# MyLightThingy.net
KiCad netlist of a schematic drawn in EasyEDA Pro
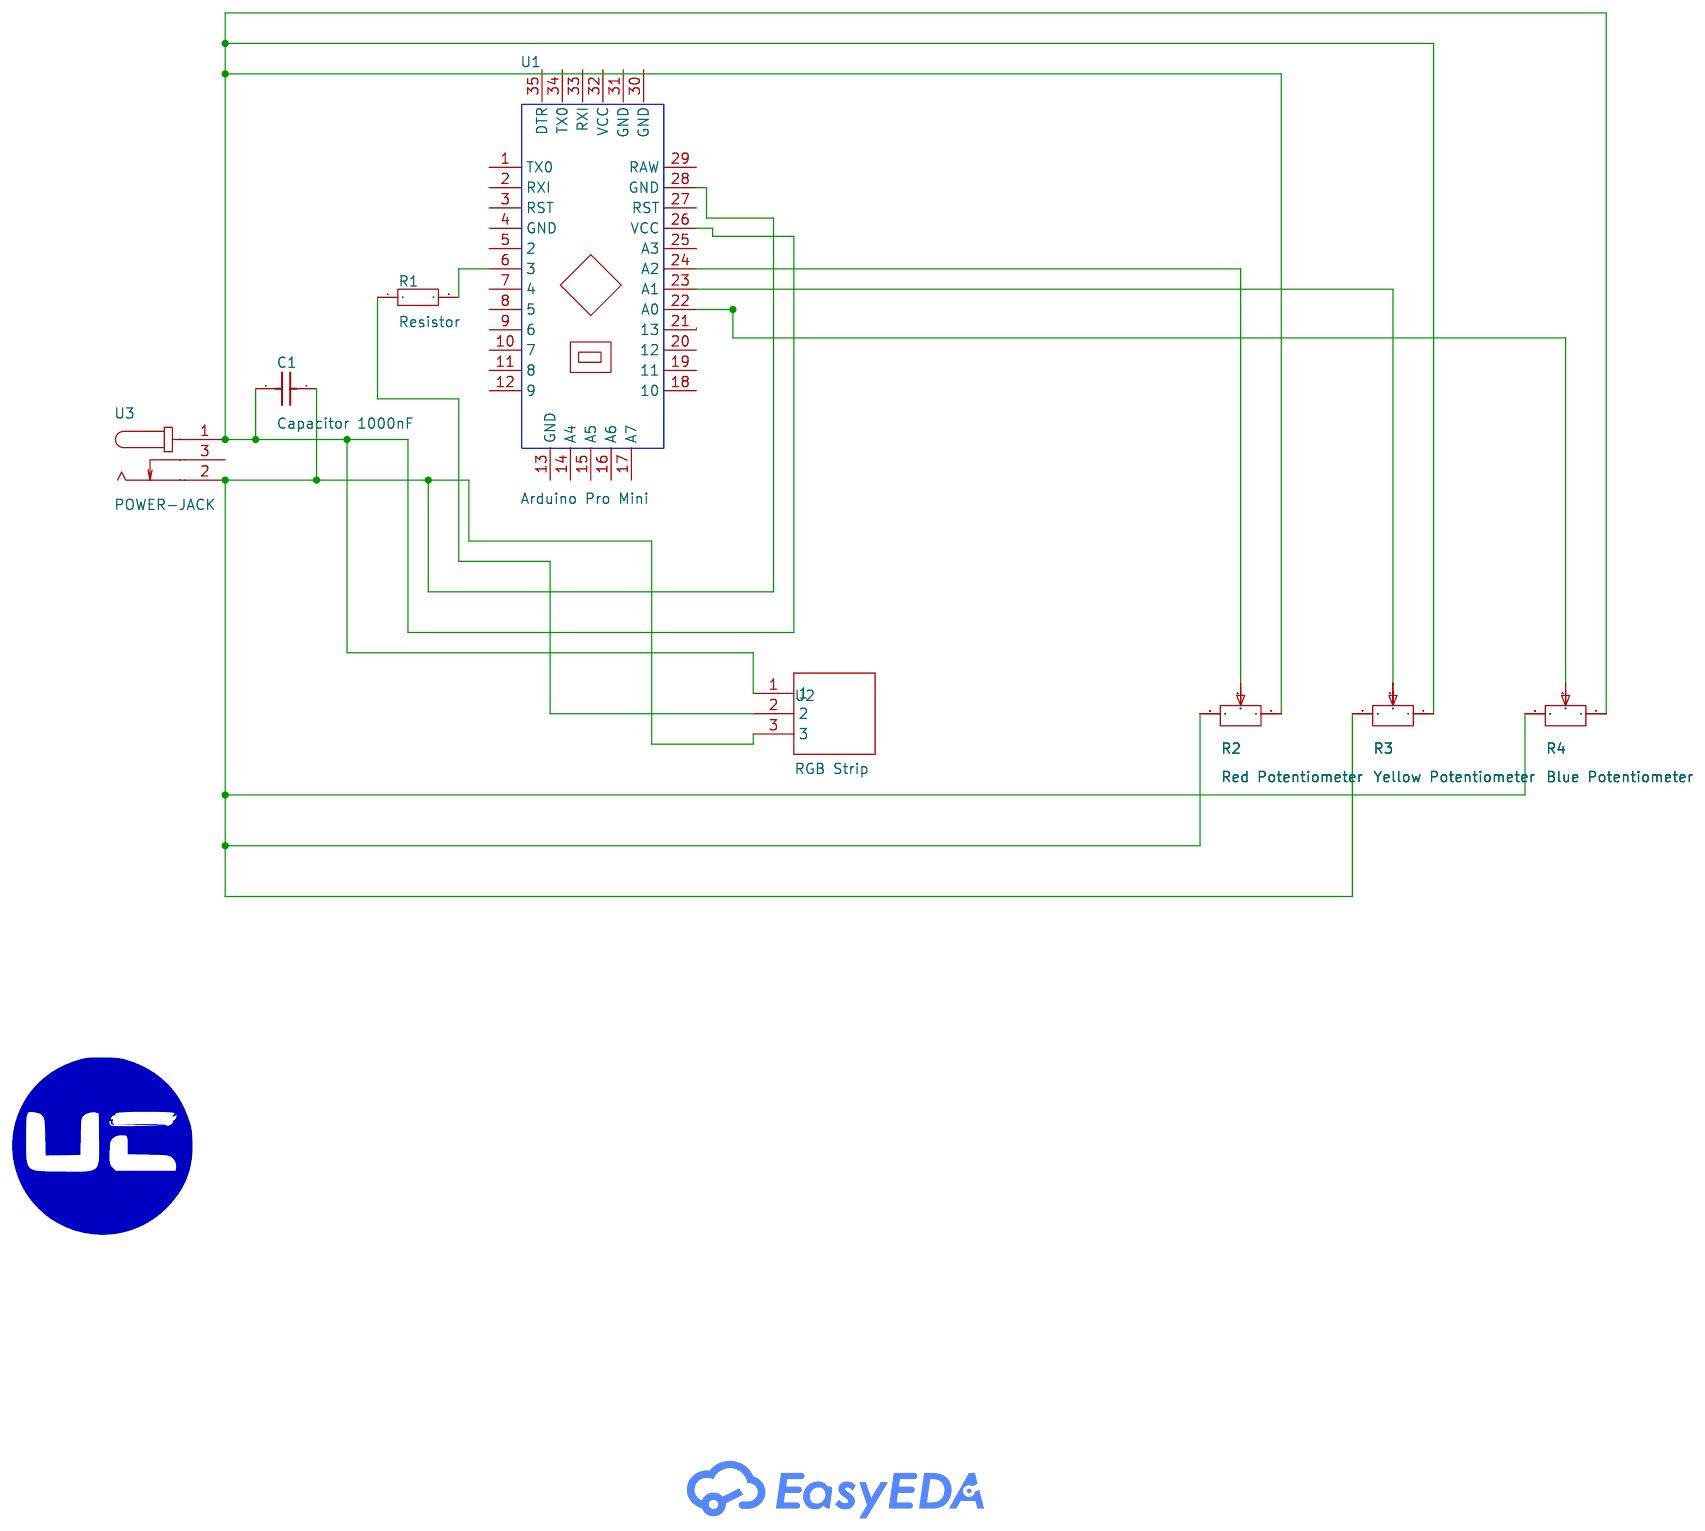
[diagram p0: schematic sheet]

(export (version "E")
  (design (tool "Eeschema 10.0.6"))
  (components
    (comp (ref "C1")
      (value "Capacitor 1000nF")
      (footprint "easyedapro:CAP-TH_L7.2-W2.5-P5.00-D0.5_224CL0016")
      (description "1pf - 100nf box film cap")
      (fields
        (field (name "Manufacturer Part") "CL21B104KCFNNNE")
        (field (name "Manufacturer") "SAMSUNG(三星)")
      )
      (libsource (lib "easyedapro") (part "Avg Film cap"))
    )
    (comp (ref "R1")
      (value "Resistor")
      (footprint "easyedapro:Resistor 1/8w 7mm metal film")
      (fields
        (field (name "Manufacturer Part") "1206W4F1002T5E")
        (field (name "Manufacturer") "UNI-ROYAL(Uniroyal Elec)")
      )
      (libsource (lib "easyedapro") (part "resistor"))
    )
    (comp (ref "R2")
      (value "10kΩ")
      (footprint "easyedapro:RES-ADJ-TH_RK1631110TT3")
      (description "Resistance: Tolerance:±20% Tolerance:±20% Power(Watts):50mW Turns:- Rated Voltage:5V")
      (fields
        (field (name "Manufacturer Part") "RK1631110TT3")
        (field (name "Manufacturer") "ALPSALPINE(阿尔卑斯阿尔派)")
      )
      (libsource (lib "easyedapro") (part "Potentiometer"))
    )
    (comp (ref "R3")
      (value "10kΩ")
      (footprint "easyedapro:RES-ADJ-TH_RK1631110TT3")
      (description "Resistance: Tolerance:±20% Tolerance:±20% Power(Watts):50mW Turns:- Rated Voltage:5V")
      (fields
        (field (name "Manufacturer Part") "RK1631110TT3")
        (field (name "Manufacturer") "ALPSALPINE(阿尔卑斯阿尔派)")
      )
      (libsource (lib "easyedapro") (part "Potentiometer"))
    )
    (comp (ref "R4")
      (value "10kΩ")
      (footprint "easyedapro:RES-ADJ-TH_RK1631110TT3")
      (description "Resistance: Tolerance:±20% Tolerance:±20% Power(Watts):50mW Turns:- Rated Voltage:5V")
      (fields
        (field (name "Manufacturer Part") "RK1631110TT3")
        (field (name "Manufacturer") "ALPSALPINE(阿尔卑斯阿尔派)")
      )
      (libsource (lib "easyedapro") (part "Potentiometer"))
    )
    (comp (ref "U1")
      (value "Arduino Pro Mini")
      (footprint "easyedapro:Arduino_Pro_Mini")
      (libsource (lib "easyedapro") (part "Arduino Pro Mini"))
    )
    (comp (ref "U2")
      (value "RGB Strip")
      (footprint "easyedapro:V3 pin male 3x1")
      (fields (field (name "Manufacturer") "TE Connectivity"))
      (libsource (lib "easyedapro") (part "V3 pin male 3x1"))
    )
    (comp (ref "U3")
      (value "POWER-JACK")
      (footprint "easyedapro:DC-IN-TH_POWER-JACK")
      (libsource (lib "easyedapro") (part "POWER-JACK"))
    )
  )
  (nets
    (net (code "1") (name "Net-(C1-Pad1)") (class "Default")
      (node (ref "C1") (pin "1") (pinfunction "1_1") (pintype "input"))
      (node (ref "R2") (pin "1") (pinfunction "1_1") (pintype "input"))
      (node (ref "R3") (pin "1") (pinfunction "1_1") (pintype "input"))
      (node (ref "R4") (pin "1") (pinfunction "1_1") (pintype "input"))
      (node (ref "U1") (pin "26") (pinfunction "VCC_26") (pintype "input"))
      (node (ref "U2") (pin "1") (pinfunction "1_1") (pintype "bidirectional"))
      (node (ref "U3") (pin "1") (pinfunction "1_1") (pintype "unspecified"))
    )
    (net (code "2") (name "Net-(C1-Pad2)") (class "Default")
      (node (ref "C1") (pin "2") (pinfunction "2_2") (pintype "input"))
      (node (ref "R2") (pin "3") (pinfunction "3_3") (pintype "input"))
      (node (ref "R3") (pin "3") (pinfunction "3_3") (pintype "input"))
      (node (ref "R4") (pin "3") (pinfunction "3_3") (pintype "input"))
      (node (ref "U1") (pin "28") (pinfunction "GND_28") (pintype "input"))
      (node (ref "U2") (pin "3") (pinfunction "3_3") (pintype "bidirectional"))
      (node (ref "U3") (pin "2") (pinfunction "2_2") (pintype "unspecified"))
    )
    (net (code "3") (name "Net-(R1-Pad1)") (class "Default")
      (node (ref "R1") (pin "1") (pinfunction "1_1") (pintype "input"))
      (node (ref "U2") (pin "2") (pinfunction "2_2") (pintype "bidirectional"))
    )
    (net (code "4") (name "Net-(U1-3)") (class "Default")
      (node (ref "R1") (pin "2") (pinfunction "2_2") (pintype "input"))
      (node (ref "U1") (pin "6") (pinfunction "3_6") (pintype "input"))
    )
    (net (code "5") (name "Net-(U1-A0)") (class "Default")
      (node (ref "R4") (pin "2") (pinfunction "2_2") (pintype "input"))
      (node (ref "U1") (pin "22") (pinfunction "A0_22") (pintype "input"))
    )
    (net (code "6") (name "Net-(U1-A1)") (class "Default")
      (node (ref "R3") (pin "2") (pinfunction "2_2") (pintype "input"))
      (node (ref "U1") (pin "23") (pinfunction "A1_23") (pintype "input"))
    )
    (net (code "7") (name "Net-(U1-A2)") (class "Default")
      (node (ref "R2") (pin "2") (pinfunction "2_2") (pintype "input"))
      (node (ref "U1") (pin "24") (pinfunction "A2_24") (pintype "input"))
    )
    (net (code "8") (name "unconnected-(U1-2-Pad5)") (class "Default")
      (node (ref "U1") (pin "5") (pinfunction "2_5") (pintype "input"))
    )
    (net (code "9") (name "unconnected-(U1-4-Pad7)") (class "Default")
      (node (ref "U1") (pin "7") (pinfunction "4_7") (pintype "input"))
    )
    (net (code "10") (name "unconnected-(U1-5-Pad8)") (class "Default")
      (node (ref "U1") (pin "8") (pinfunction "5_8") (pintype "input"))
    )
    (net (code "11") (name "unconnected-(U1-6-Pad9)") (class "Default")
      (node (ref "U1") (pin "9") (pinfunction "6_9") (pintype "input"))
    )
    (net (code "12") (name "unconnected-(U1-7-Pad10)") (class "Default")
      (node (ref "U1") (pin "10") (pinfunction "7_10") (pintype "input"))
    )
    (net (code "13") (name "unconnected-(U1-8-Pad11)") (class "Default")
      (node (ref "U1") (pin "11") (pinfunction "8_11") (pintype "input"))
    )
    (net (code "14") (name "unconnected-(U1-9-Pad12)") (class "Default")
      (node (ref "U1") (pin "12") (pinfunction "9_12") (pintype "input"))
    )
    (net (code "15") (name "unconnected-(U1-10-Pad18)") (class "Default")
      (node (ref "U1") (pin "18") (pinfunction "10_18") (pintype "input"))
    )
    (net (code "16") (name "unconnected-(U1-11-Pad19)") (class "Default")
      (node (ref "U1") (pin "19") (pinfunction "11_19") (pintype "input"))
    )
    (net (code "17") (name "unconnected-(U1-12-Pad20)") (class "Default")
      (node (ref "U1") (pin "20") (pinfunction "12_20") (pintype "input"))
    )
    (net (code "18") (name "unconnected-(U1-13-Pad21)") (class "Default")
      (node (ref "U1") (pin "21") (pinfunction "13_21") (pintype "input"))
    )
    (net (code "19") (name "unconnected-(U1-A3-Pad25)") (class "Default")
      (node (ref "U1") (pin "25") (pinfunction "A3_25") (pintype "input"))
    )
    (net (code "20") (name "unconnected-(U1-A4-Pad14)") (class "Default")
      (node (ref "U1") (pin "14") (pinfunction "A4_14") (pintype "bidirectional"))
    )
    (net (code "21") (name "unconnected-(U1-A5-Pad15)") (class "Default")
      (node (ref "U1") (pin "15") (pinfunction "A5_15") (pintype "bidirectional"))
    )
    (net (code "22") (name "unconnected-(U1-A6-Pad16)") (class "Default")
      (node (ref "U1") (pin "16") (pinfunction "A6_16") (pintype "bidirectional"))
    )
    (net (code "23") (name "unconnected-(U1-A7-Pad17)") (class "Default")
      (node (ref "U1") (pin "17") (pinfunction "A7_17") (pintype "bidirectional"))
    )
    (net (code "24") (name "unconnected-(U1-DTR-Pad35)") (class "Default")
      (node (ref "U1") (pin "35") (pinfunction "DTR_35") (pintype "input"))
    )
    (net (code "25") (name "unconnected-(U1-GND-Pad4)") (class "Default")
      (node (ref "U1") (pin "4") (pinfunction "GND_4") (pintype "input"))
    )
    (net (code "26") (name "unconnected-(U1-GND-Pad13)") (class "Default")
      (node (ref "U1") (pin "13") (pinfunction "GND_13") (pintype "bidirectional"))
    )
    (net (code "27") (name "unconnected-(U1-GND-Pad30)") (class "Default")
      (node (ref "U1") (pin "30") (pinfunction "GND_30") (pintype "input"))
    )
    (net (code "28") (name "unconnected-(U1-GND-Pad31)") (class "Default")
      (node (ref "U1") (pin "31") (pinfunction "GND_31") (pintype "input"))
    )
    (net (code "29") (name "unconnected-(U1-RAW-Pad29)") (class "Default")
      (node (ref "U1") (pin "29") (pinfunction "RAW_29") (pintype "input"))
    )
    (net (code "30") (name "unconnected-(U1-RST-Pad3)") (class "Default")
      (node (ref "U1") (pin "3") (pinfunction "RST_3") (pintype "input"))
    )
    (net (code "31") (name "unconnected-(U1-RST-Pad27)") (class "Default")
      (node (ref "U1") (pin "27") (pinfunction "RST_27") (pintype "input"))
    )
    (net (code "32") (name "unconnected-(U1-RXI-Pad2)") (class "Default")
      (node (ref "U1") (pin "2") (pinfunction "RXI_2") (pintype "input"))
    )
    (net (code "33") (name "unconnected-(U1-RXI-Pad33)") (class "Default")
      (node (ref "U1") (pin "33") (pinfunction "RXI_33") (pintype "input"))
    )
    (net (code "34") (name "unconnected-(U1-TX0-Pad1)") (class "Default")
      (node (ref "U1") (pin "1") (pinfunction "TX0_1") (pintype "input"))
    )
    (net (code "35") (name "unconnected-(U1-TX0-Pad34)") (class "Default")
      (node (ref "U1") (pin "34") (pinfunction "TX0_34") (pintype "input"))
    )
    (net (code "36") (name "unconnected-(U1-VCC-Pad32)") (class "Default")
      (node (ref "U1") (pin "32") (pinfunction "VCC_32") (pintype "input"))
    )
    (net (code "37") (name "unconnected-(U3-Pad3)") (class "Default")
      (node (ref "U3") (pin "3") (pinfunction "3_3") (pintype "unspecified"))
    )
  )
)
